# SpectraPCB.net
KiCad netlist of a schematic drawn in EAGLE
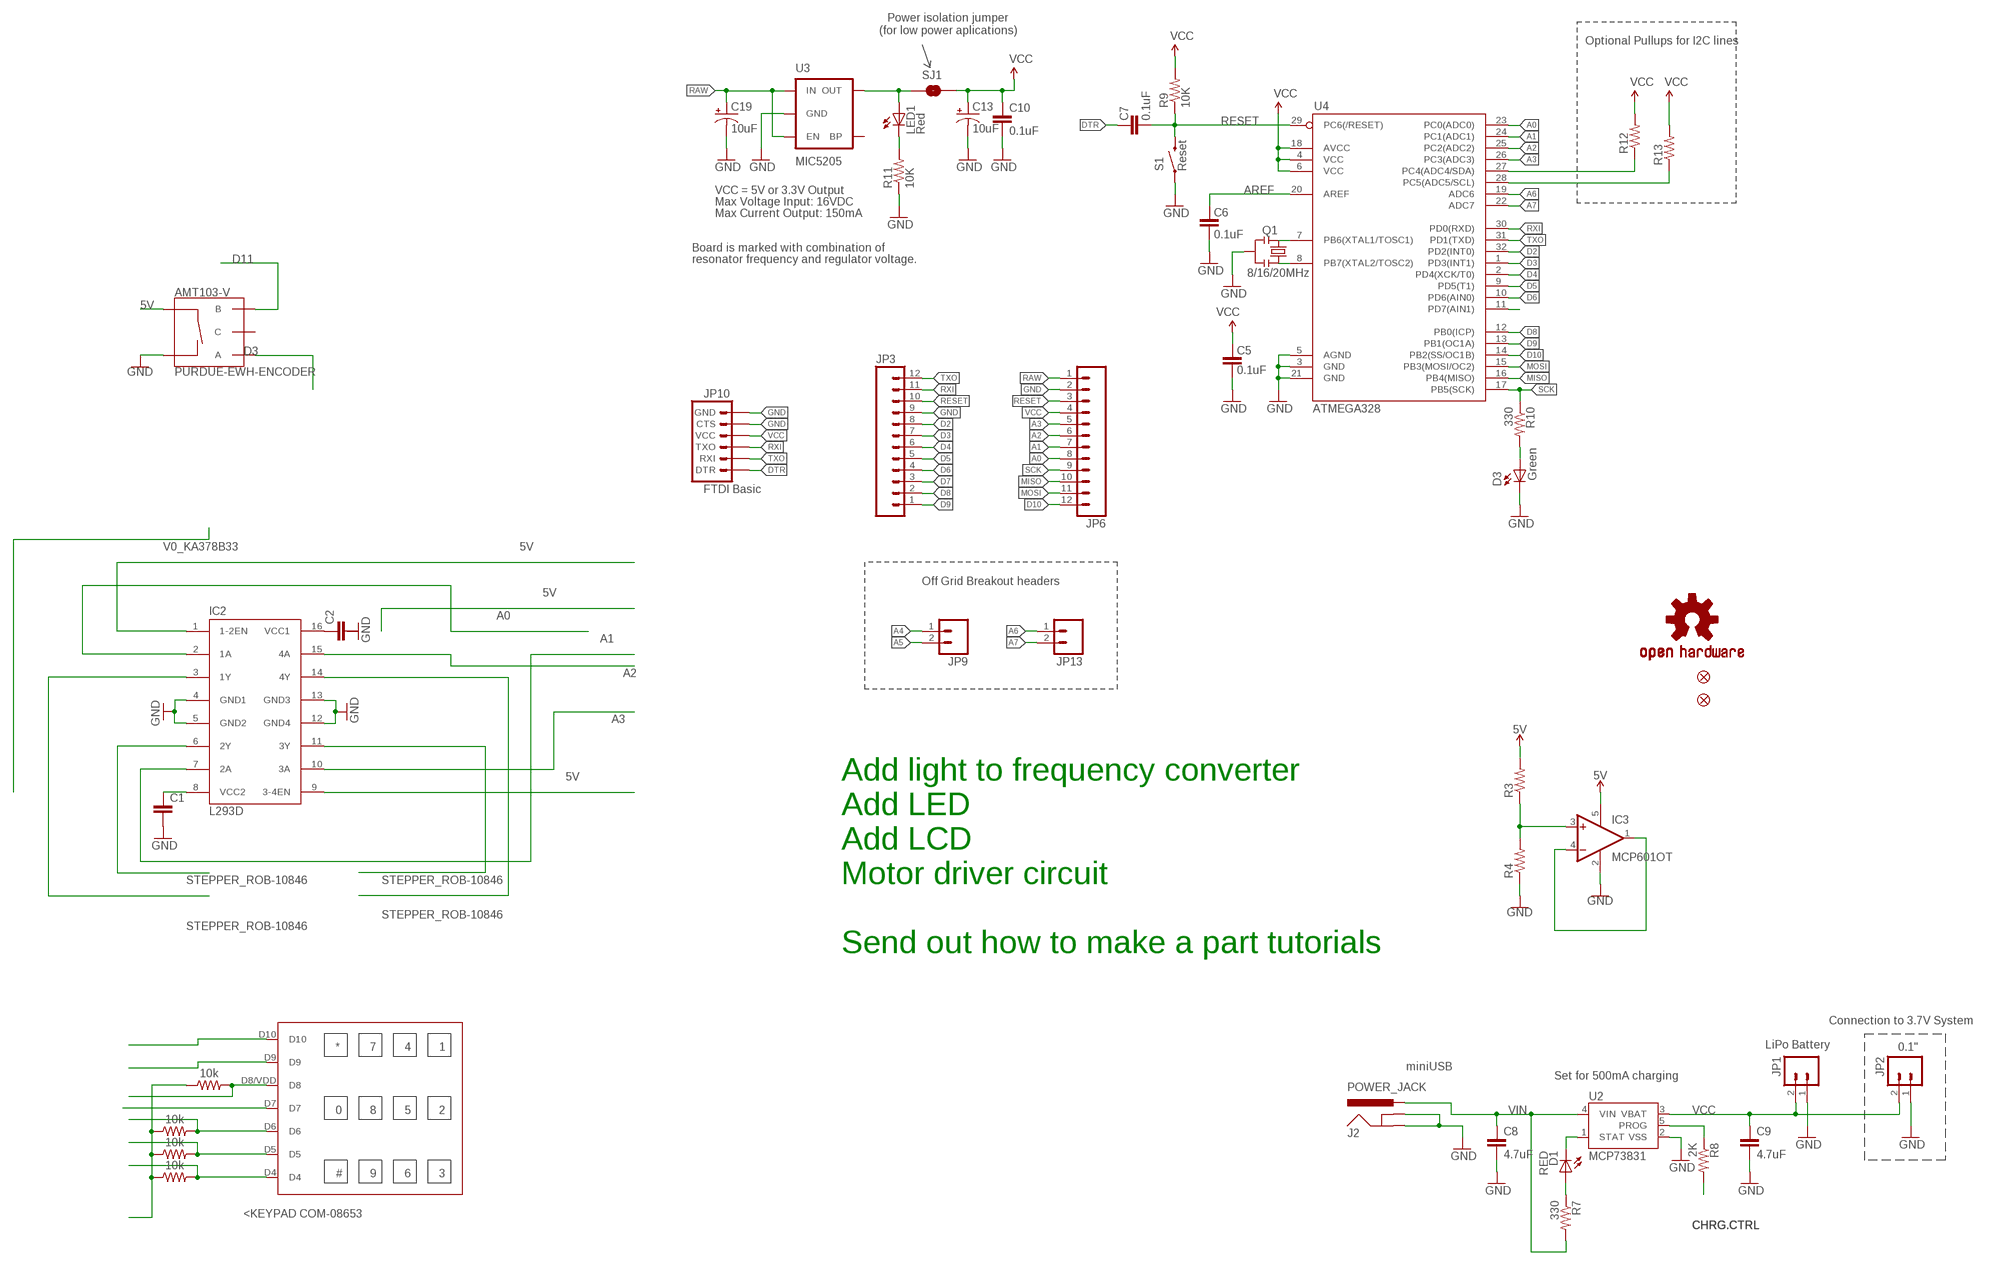
[diagram p0: schematic, sheet 1]

(export (version "E")
  (design (tool "Eeschema 10.0.6"))
  (components
    (comp (ref "AMT103-V")
      (value "PURDUE-EWH-ENCODER")
      (footprint "eagle-import:PURDUE-EWH-ENCODER")
      (libsource (lib "eagle-import") (part "PURDUE-EWH-ENCODER"))
    )
    (comp (ref "C1")
      (value "C-EUC0603")
      (footprint "eagle-import:C0603")
      (libsource (lib "eagle-import") (part "C-EUC0603"))
    )
    (comp (ref "C2")
      (value "C-EUC0402")
      (footprint "eagle-import:C0402")
      (libsource (lib "eagle-import") (part "C-EUC0402"))
    )
    (comp (ref "C5")
      (value "0.1uF")
      (footprint "eagle-import:0603-CAP")
      (libsource (lib "eagle-import") (part "CAP0603-CAP"))
    )
    (comp (ref "C6")
      (value "0.1uF")
      (footprint "eagle-import:0603-CAP")
      (libsource (lib "eagle-import") (part "CAP0603-CAP"))
    )
    (comp (ref "C7")
      (value "0.1uF")
      (footprint "eagle-import:0603-CAP")
      (libsource (lib "eagle-import") (part "CAP0603-CAP"))
    )
    (comp (ref "C8")
      (value "4.7uF")
      (footprint "eagle-import:0402-CAP")
      (libsource (lib "eagle-import") (part "CAP0402-CAP"))
    )
    (comp (ref "C9")
      (value "4.7uF")
      (footprint "eagle-import:0402-CAP")
      (libsource (lib "eagle-import") (part "CAP0402-CAP"))
    )
    (comp (ref "C10")
      (value "0.1uF")
      (footprint "eagle-import:0603-CAP")
      (libsource (lib "eagle-import") (part "CAP0603-CAP"))
    )
    (comp (ref "C13")
      (value "10uF")
      (footprint "eagle-import:EIA3216")
      (libsource (lib "eagle-import") (part "CAP_POL1206"))
    )
    (comp (ref "C19")
      (value "10uF")
      (footprint "eagle-import:EIA3216")
      (libsource (lib "eagle-import") (part "CAP_POL1206"))
    )
    (comp (ref "D1")
      (value "RED")
      (footprint "eagle-import:LED-0603")
      (libsource (lib "eagle-import") (part "LED0603"))
    )
    (comp (ref "D3")
      (value "Green")
      (footprint "eagle-import:0603-LED-ALT1")
      (libsource (lib "eagle-import") (part "LED"))
    )
    (comp (ref "IC2")
      (value "L293D")
      (footprint "eagle-import:DIL16")
      (libsource (lib "eagle-import") (part "L293D"))
    )
    (comp (ref "IC3")
      (value "MCP601OT")
      (footprint "eagle-import:SOT23-5")
      (libsource (lib "eagle-import") (part "MCP601OT"))
    )
    (comp (ref "J2")
      (value "POWER_JACK")
      (footprint "eagle-import:POWER_JACK_PTH")
      (libsource (lib "eagle-import") (part "POWER_JACK"))
    )
    (comp (ref "JP1")
      (value "LiPo Battery")
      (footprint "eagle-import:JST-2-SMD")
      (libsource (lib "eagle-import") (part "M02-JST-2MM-SMT"))
    )
    (comp (ref "JP2")
      (value "M02PTH")
      (footprint "eagle-import:1X02")
      (libsource (lib "eagle-import") (part "M02PTH"))
    )
    (comp (ref "JP3")
      (value "M12PTH")
      (footprint "eagle-import:1X12")
      (libsource (lib "eagle-import") (part "M12PTH"))
    )
    (comp (ref "JP6")
      (value "M12PTH")
      (footprint "eagle-import:1X12")
      (libsource (lib "eagle-import") (part "M12PTH"))
    )
    (comp (ref "JP9")
      (value "M02PTH")
      (footprint "eagle-import:1X02")
      (libsource (lib "eagle-import") (part "M02PTH"))
    )
    (comp (ref "JP10")
      (value "FTDI Basic")
      (footprint "eagle-import:1X06")
      (libsource (lib "eagle-import") (part "ARDUINO_SERIAL_PROGRAMPTH"))
    )
    (comp (ref "JP11")
      (value "FIDUCIALUFIDUCIAL")
      (footprint "eagle-import:MICRO-FIDUCIAL")
      (libsource (lib "eagle-import") (part "FIDUCIALUFIDUCIAL"))
    )
    (comp (ref "JP12")
      (value "FIDUCIALUFIDUCIAL")
      (footprint "eagle-import:MICRO-FIDUCIAL")
      (libsource (lib "eagle-import") (part "FIDUCIALUFIDUCIAL"))
    )
    (comp (ref "JP13")
      (value "M02PTH")
      (footprint "eagle-import:1X02")
      (libsource (lib "eagle-import") (part "M02PTH"))
    )
    (comp (ref "LED1")
      (value "Red")
      (footprint "eagle-import:0603-LED-ALT1")
      (libsource (lib "eagle-import") (part "LED"))
    )
    (comp (ref "Q1")
      (value "8/16/20MHz")
      (footprint "eagle-import:RESONATOR-SMD-1_1")
      (libsource (lib "eagle-import") (part "RESONATOR1{colon}1"))
    )
    (comp (ref "R1")
      (value "10k")
      (footprint "eagle-import:0603")
      (libsource (lib "eagle-import") (part "10KOHM-0603-1/10W-1%"))
    )
    (comp (ref "R2")
      (value "10k")
      (footprint "eagle-import:0603")
      (libsource (lib "eagle-import") (part "10KOHM-0603-1/10W-1%"))
    )
    (comp (ref "R3")
      (value "R-US_R0402")
      (footprint "eagle-import:R0402")
      (libsource (lib "eagle-import") (part "R-US_R0402"))
    )
    (comp (ref "R4")
      (value "R-US_R0402")
      (footprint "eagle-import:R0402")
      (libsource (lib "eagle-import") (part "R-US_R0402"))
    )
    (comp (ref "R5")
      (value "10k")
      (footprint "eagle-import:0603")
      (libsource (lib "eagle-import") (part "10KOHM-0603-1/10W-1%"))
    )
    (comp (ref "R6")
      (value "10k")
      (footprint "eagle-import:0603")
      (libsource (lib "eagle-import") (part "10KOHM-0603-1/10W-1%"))
    )
    (comp (ref "R7")
      (value "330")
      (footprint "eagle-import:0402-RES")
      (libsource (lib "eagle-import") (part "RESISTOR0402-RES"))
    )
    (comp (ref "R8")
      (value "2K")
      (footprint "eagle-import:0402-RES")
      (libsource (lib "eagle-import") (part "RESISTOR0402-RES"))
    )
    (comp (ref "R9")
      (value "10K")
      (footprint "eagle-import:0603-RES")
      (libsource (lib "eagle-import") (part "RESISTOR0603-RES"))
    )
    (comp (ref "R10")
      (value "330")
      (footprint "eagle-import:0603-RES")
      (libsource (lib "eagle-import") (part "RESISTOR0603-RES"))
    )
    (comp (ref "R11")
      (value "10K")
      (footprint "eagle-import:0603-RES")
      (libsource (lib "eagle-import") (part "RESISTOR0603-RES"))
    )
    (comp (ref "R12")
      (value "RESISTOR0603-RES")
      (footprint "eagle-import:0603-RES")
      (libsource (lib "eagle-import") (part "RESISTOR0603-RES"))
    )
    (comp (ref "R13")
      (value "RESISTOR0603-RES")
      (footprint "eagle-import:0603-RES")
      (libsource (lib "eagle-import") (part "RESISTOR0603-RES"))
    )
    (comp (ref "S1")
      (value "Reset")
      (footprint "eagle-import:TACTILE-SWITCH-SMD-ALT01")
      (libsource (lib "eagle-import") (part "SWITCH-MOMENTARY-2SMD-ALT01"))
    )
    (comp (ref "SJ1")
      (value "SOLDERJUMPERNC")
      (footprint "eagle-import:SJ_2S")
      (libsource (lib "eagle-import") (part "SOLDERJUMPERNC"))
    )
    (comp (ref "U$1")
      (value "EWH_KEYPAD")
      (footprint "eagle-import:EWH_KEYPAD")
      (libsource (lib "eagle-import") (part "EWH_KEYPAD"))
    )
    (comp (ref "U$3")
      (value "OSHW-LOGOS")
      (footprint "eagle-import:OSHW-LOGO-S")
      (libsource (lib "eagle-import") (part "OSHW-LOGOS"))
    )
    (comp (ref "U2")
      (value "MCP73831")
      (footprint "eagle-import:SOT23-5")
      (libsource (lib "eagle-import") (part "MCP73831"))
    )
    (comp (ref "U3")
      (value "MIC5205")
      (footprint "eagle-import:SOT23-5")
      (libsource (lib "eagle-import") (part "V_REG_LDOSMD"))
    )
    (comp (ref "U4")
      (value "ATMEGA328")
      (footprint "eagle-import:TQFP32-08")
      (libsource (lib "eagle-import") (part "ATMEGA168"))
    )
  )
  (nets
    (net (code "1") (name "/AREF") (class "Default")
      (node (ref "C6") (pin "2") (pinfunction "2_2") (pintype "passive"))
      (node (ref "U4") (pin "20") (pinfunction "AREF_20") (pintype "bidirectional"))
    )
    (net (code "2") (name "/CHRG.CTRL") (class "Default")
      (node (ref "R8") (pin "2") (pinfunction "2_2") (pintype "passive"))
      (node (ref "U4") (pin "11") (pinfunction "PD7(AIN1)_11") (pintype "bidirectional"))
    )
    (net (code "3") (name "/D11") (class "Default")
      (node (ref "AMT103-V") (pin "B") (pinfunction "B_B") (pintype "bidirectional"))
    )
    (net (code "4") (name "/STEPPER_ROB-10846") (class "Default")
      (node (ref "IC2") (pin "11") (pinfunction "3Y_11") (pintype "output"))
      (node (ref "IC2") (pin "14") (pinfunction "4Y_14") (pintype "output"))
      (node (ref "IC2") (pin "3") (pinfunction "1Y_3") (pintype "output"))
      (node (ref "IC2") (pin "6") (pinfunction "2Y_6") (pintype "output"))
    )
    (net (code "6") (name "/VIN") (class "Default")
      (node (ref "C8") (pin "1") (pinfunction "1_1") (pintype "passive"))
      (node (ref "J2") (pin "PWR") (pinfunction "PWR_PWR") (pintype "bidirectional"))
      (node (ref "R7") (pin "2") (pinfunction "2_2") (pintype "passive"))
      (node (ref "U2") (pin "4") (pinfunction "VIN_4") (pintype "power_in"))
    )
    (net (code "7") (name "5V") (class "Default")
      (node (ref "AMT103-V") (pin "SW+") (pinfunction "SW+_SW+") (pintype "bidirectional"))
      (node (ref "IC2") (pin "1") (pinfunction "1-2EN_1") (pintype "input"))
      (node (ref "IC2") (pin "9") (pinfunction "3-4EN_9") (pintype "input"))
      (node (ref "IC3") (pin "5") (pinfunction "V+_5") (pintype "power_in"))
      (node (ref "R3") (pin "2") (pinfunction "2_2") (pintype "passive"))
    )
    (net (code "8") (name "A0") (class "Default")
      (node (ref "IC2") (pin "2") (pinfunction "1A_2") (pintype "input"))
      (node (ref "JP6") (pin "8") (pinfunction "8_8") (pintype "passive"))
      (node (ref "U4") (pin "23") (pinfunction "PC0(ADC0)_23") (pintype "bidirectional"))
    )
    (net (code "9") (name "A1") (class "Default")
      (node (ref "IC2") (pin "7") (pinfunction "2A_7") (pintype "input"))
      (node (ref "JP6") (pin "7") (pinfunction "7_7") (pintype "passive"))
      (node (ref "U4") (pin "24") (pinfunction "PC1(ADC1)_24") (pintype "bidirectional"))
    )
    (net (code "10") (name "A2") (class "Default")
      (node (ref "IC2") (pin "15") (pinfunction "4A_15") (pintype "input"))
      (node (ref "JP6") (pin "6") (pinfunction "6_6") (pintype "passive"))
      (node (ref "U4") (pin "25") (pinfunction "PC2(ADC2)_25") (pintype "bidirectional"))
    )
    (net (code "11") (name "A3") (class "Default")
      (node (ref "IC2") (pin "10") (pinfunction "3A_10") (pintype "input"))
      (node (ref "JP6") (pin "5") (pinfunction "5_5") (pintype "passive"))
      (node (ref "U4") (pin "26") (pinfunction "PC3(ADC3)_26") (pintype "bidirectional"))
    )
    (net (code "12") (name "A4") (class "Default")
      (node (ref "JP9") (pin "1") (pinfunction "1_1") (pintype "passive"))
      (node (ref "R12") (pin "1") (pinfunction "1_1") (pintype "passive"))
      (node (ref "U4") (pin "27") (pinfunction "PC4(ADC4/SDA)_27") (pintype "bidirectional"))
    )
    (net (code "13") (name "A5") (class "Default")
      (node (ref "JP9") (pin "2") (pinfunction "2_2") (pintype "passive"))
      (node (ref "R13") (pin "1") (pinfunction "1_1") (pintype "passive"))
      (node (ref "U4") (pin "28") (pinfunction "PC5(ADC5/SCL)_28") (pintype "bidirectional"))
    )
    (net (code "14") (name "A6") (class "Default")
      (node (ref "JP13") (pin "1") (pinfunction "1_1") (pintype "passive"))
      (node (ref "U4") (pin "19") (pinfunction "ADC6_19") (pintype "bidirectional"))
    )
    (net (code "15") (name "A7") (class "Default")
      (node (ref "JP13") (pin "2") (pinfunction "2_2") (pintype "passive"))
      (node (ref "U4") (pin "22") (pinfunction "ADC7_22") (pintype "bidirectional"))
    )
    (net (code "16") (name "D2") (class "Default")
      (node (ref "JP3") (pin "8") (pinfunction "8_8") (pintype "passive"))
      (node (ref "U4") (pin "32") (pinfunction "PD2(INT0)_32") (pintype "bidirectional"))
    )
    (net (code "17") (name "D3") (class "Default")
      (node (ref "AMT103-V") (pin "A") (pinfunction "A_A") (pintype "bidirectional"))
      (node (ref "JP3") (pin "7") (pinfunction "7_7") (pintype "passive"))
      (node (ref "U4") (pin "1") (pinfunction "PD3(INT1)_1") (pintype "bidirectional"))
    )
    (net (code "18") (name "D4") (class "Default")
      (node (ref "JP3") (pin "6") (pinfunction "6_6") (pintype "passive"))
      (node (ref "U4") (pin "2") (pinfunction "PD4(XCK/T0)_2") (pintype "bidirectional"))
    )
    (net (code "19") (name "D5") (class "Default")
      (node (ref "JP3") (pin "5") (pinfunction "5_5") (pintype "passive"))
      (node (ref "U4") (pin "9") (pinfunction "PD5(T1)_9") (pintype "bidirectional"))
    )
    (net (code "20") (name "D6") (class "Default")
      (node (ref "JP3") (pin "4") (pinfunction "4_4") (pintype "passive"))
      (node (ref "U4") (pin "10") (pinfunction "PD6(AIN0)_10") (pintype "bidirectional"))
    )
    (net (code "21") (name "D7") (class "Default")
      (node (ref "JP3") (pin "3") (pinfunction "3_3") (pintype "passive"))
    )
    (net (code "22") (name "D8") (class "Default")
      (node (ref "JP3") (pin "2") (pinfunction "2_2") (pintype "passive"))
      (node (ref "U4") (pin "12") (pinfunction "PB0(ICP)_12") (pintype "bidirectional"))
    )
    (net (code "23") (name "D9") (class "Default")
      (node (ref "JP3") (pin "1") (pinfunction "1_1") (pintype "passive"))
      (node (ref "U4") (pin "13") (pinfunction "PB1(OC1A)_13") (pintype "bidirectional"))
    )
    (net (code "24") (name "D10") (class "Default")
      (node (ref "JP6") (pin "12") (pinfunction "12_12") (pintype "passive"))
      (node (ref "U4") (pin "14") (pinfunction "PB2(SS/OC1B)_14") (pintype "bidirectional"))
    )
    (net (code "25") (name "DTR") (class "Default")
      (node (ref "C7") (pin "2") (pinfunction "2_2") (pintype "passive"))
      (node (ref "JP10") (pin "1") (pinfunction "DTR_1") (pintype "passive"))
    )
    (net (code "26") (name "GND") (class "Default")
      (node (ref "AMT103-V") (pin "SW-") (pinfunction "SW-_SW-") (pintype "bidirectional"))
      (node (ref "C1") (pin "2") (pinfunction "2_2") (pintype "passive"))
      (node (ref "C10") (pin "2") (pinfunction "2_2") (pintype "passive"))
      (node (ref "C13") (pin "C") (pinfunction "-_C") (pintype "passive"))
      (node (ref "C19") (pin "C") (pinfunction "-_C") (pintype "passive"))
      (node (ref "C5") (pin "1") (pinfunction "1_1") (pintype "passive"))
      (node (ref "C6") (pin "1") (pinfunction "1_1") (pintype "passive"))
      (node (ref "C8") (pin "2") (pinfunction "2_2") (pintype "passive"))
      (node (ref "C9") (pin "2") (pinfunction "2_2") (pintype "passive"))
      (node (ref "D3") (pin "C") (pinfunction "C_C") (pintype "passive"))
      (node (ref "IC2") (pin "12") (pinfunction "GND4_12") (pintype "power_in"))
      (node (ref "IC2") (pin "13") (pinfunction "GND3_13") (pintype "power_in"))
      (node (ref "IC2") (pin "4") (pinfunction "GND1_4") (pintype "power_in"))
      (node (ref "IC2") (pin "5") (pinfunction "GND2_5") (pintype "power_in"))
      (node (ref "IC3") (pin "2") (pinfunction "V-_2") (pintype "power_in"))
      (node (ref "J2") (pin "GND") (pinfunction "GND_GND") (pintype "bidirectional"))
      (node (ref "J2") (pin "GNDBREAK") (pinfunction "GNDBREAK_GNDBREAK") (pintype "bidirectional"))
      (node (ref "JP1") (pin "1") (pinfunction "1_1") (pintype "passive"))
      (node (ref "JP10") (pin "5") (pinfunction "CTS_5") (pintype "passive"))
      (node (ref "JP10") (pin "6") (pinfunction "GND_6") (pintype "passive"))
      (node (ref "JP2") (pin "1") (pinfunction "1_1") (pintype "passive"))
      (node (ref "JP3") (pin "9") (pinfunction "9_9") (pintype "passive"))
      (node (ref "JP6") (pin "2") (pinfunction "2_2") (pintype "passive"))
      (node (ref "Q1") (pin "2") (pinfunction "2_2") (pintype "passive"))
      (node (ref "R11") (pin "1") (pinfunction "1_1") (pintype "passive"))
      (node (ref "R4") (pin "1") (pinfunction "1_1") (pintype "passive"))
      (node (ref "S1") (pin "1") (pinfunction "1_1") (pintype "passive"))
      (node (ref "S1") (pin "2") (pinfunction "1_2") (pintype "passive"))
      (node (ref "U2") (pin "2") (pinfunction "VSS_2") (pintype "power_in"))
      (node (ref "U3") (pin "2") (pinfunction "GND_2") (pintype "input"))
      (node (ref "U4") (pin "21") (pinfunction "GND_21") (pintype "bidirectional"))
      (node (ref "U4") (pin "3") (pinfunction "GND_3") (pintype "bidirectional"))
      (node (ref "U4") (pin "5") (pinfunction "AGND_5") (pintype "bidirectional"))
    )
    (net (code "27") (name "MISO") (class "Default")
      (node (ref "JP6") (pin "10") (pinfunction "10_10") (pintype "passive"))
      (node (ref "U4") (pin "16") (pinfunction "PB4(MISO)_16") (pintype "bidirectional"))
    )
    (net (code "28") (name "MOSI") (class "Default")
      (node (ref "JP6") (pin "11") (pinfunction "11_11") (pintype "passive"))
      (node (ref "U4") (pin "15") (pinfunction "PB3(MOSI/OC2)_15") (pintype "bidirectional"))
    )
    (net (code "29") (name "Net-(D1-PadA)") (class "Default")
      (node (ref "D1") (pin "A") (pinfunction "A_A") (pintype "passive"))
      (node (ref "R7") (pin "1") (pinfunction "1_1") (pintype "passive"))
    )
    (net (code "30") (name "Net-(D3-PadA)") (class "Default")
      (node (ref "D3") (pin "A") (pinfunction "A_A") (pintype "passive"))
      (node (ref "R10") (pin "2") (pinfunction "2_2") (pintype "passive"))
    )
    (net (code "31") (name "Net-(IC2-VCC1)") (class "Default")
      (node (ref "C2") (pin "1") (pinfunction "1_1") (pintype "passive"))
      (node (ref "IC2") (pin "16") (pinfunction "VCC1_16") (pintype "power_in"))
    )
    (net (code "32") (name "Net-(IC2-VCC2)") (class "Default")
      (node (ref "C1") (pin "1") (pinfunction "1_1") (pintype "passive"))
      (node (ref "IC2") (pin "8") (pinfunction "VCC2_8") (pintype "power_in"))
    )
    (net (code "33") (name "Net-(IC3-+IN)") (class "Default")
      (node (ref "IC3") (pin "3") (pinfunction "+IN_3") (pintype "input"))
      (node (ref "R3") (pin "1") (pinfunction "1_1") (pintype "passive"))
      (node (ref "R4") (pin "2") (pinfunction "2_2") (pintype "passive"))
    )
    (net (code "34") (name "Net-(IC3--IN)") (class "Default")
      (node (ref "IC3") (pin "1") (pinfunction "OUT_1") (pintype "output"))
      (node (ref "IC3") (pin "4") (pinfunction "-IN_4") (pintype "input"))
    )
    (net (code "35") (name "Net-(LED1-PadC)") (class "Default")
      (node (ref "LED1") (pin "C") (pinfunction "C_C") (pintype "passive"))
      (node (ref "R11") (pin "2") (pinfunction "2_2") (pintype "passive"))
    )
    (net (code "36") (name "Net-(R1-Pad1)") (class "Default")
      (node (ref "R1") (pin "1") (pinfunction "1_1") (pintype "passive"))
      (node (ref "R2") (pin "1") (pinfunction "1_1") (pintype "passive"))
      (node (ref "R5") (pin "1") (pinfunction "1_1") (pintype "passive"))
      (node (ref "R6") (pin "1") (pinfunction "1_1") (pintype "passive"))
    )
    (net (code "37") (name "Net-(R2-Pad2)") (class "Default")
      (node (ref "R2") (pin "2") (pinfunction "2_2") (pintype "passive"))
      (node (ref "U$1") (pin "D6") (pinfunction "D6_D6") (pintype "bidirectional"))
    )
    (net (code "38") (name "Net-(R5-Pad2)") (class "Default")
      (node (ref "R5") (pin "2") (pinfunction "2_2") (pintype "passive"))
      (node (ref "U$1") (pin "D5") (pinfunction "D5_D5") (pintype "bidirectional"))
    )
    (net (code "39") (name "Net-(R6-Pad2)") (class "Default")
      (node (ref "R6") (pin "2") (pinfunction "2_2") (pintype "passive"))
      (node (ref "U$1") (pin "D4") (pinfunction "D4_D4") (pintype "bidirectional"))
    )
    (net (code "40") (name "Net-(U$1-D8)") (class "Default")
      (node (ref "R1") (pin "2") (pinfunction "2_2") (pintype "passive"))
      (node (ref "U$1") (pin "D8/VDD") (pinfunction "D8_D8/VDD") (pintype "bidirectional"))
    )
    (net (code "41") (name "Net-(U2-PROG)") (class "Default")
      (node (ref "R8") (pin "1") (pinfunction "1_1") (pintype "passive"))
      (node (ref "U2") (pin "5") (pinfunction "PROG_5") (pintype "input"))
    )
    (net (code "42") (name "Net-(U2-STAT)") (class "Default")
      (node (ref "D1") (pin "C") (pinfunction "C_C") (pintype "passive"))
      (node (ref "U2") (pin "1") (pinfunction "STAT_1") (pintype "output"))
    )
    (net (code "43") (name "Net-(U3-OUT)") (class "Default")
      (node (ref "LED1") (pin "A") (pinfunction "A_A") (pintype "passive"))
      (node (ref "SJ1") (pin "1") (pinfunction "1_1") (pintype "passive"))
      (node (ref "U3") (pin "5") (pinfunction "OUT_5") (pintype "passive"))
    )
    (net (code "44") (name "Net-(U4-PB6(XTAL1{slash}TOSC1))") (class "Default")
      (node (ref "Q1") (pin "1") (pinfunction "1_1") (pintype "passive"))
      (node (ref "U4") (pin "7") (pinfunction "PB6(XTAL1/TOSC1)_7") (pintype "bidirectional"))
    )
    (net (code "45") (name "Net-(U4-PB7(XTAL2{slash}TOSC2))") (class "Default")
      (node (ref "Q1") (pin "3") (pinfunction "3_3") (pintype "passive"))
      (node (ref "U4") (pin "8") (pinfunction "PB7(XTAL2/TOSC2)_8") (pintype "bidirectional"))
    )
    (net (code "46") (name "RAW") (class "Default")
      (node (ref "C19") (pin "A") (pinfunction "+_A") (pintype "passive"))
      (node (ref "JP6") (pin "1") (pinfunction "1_1") (pintype "passive"))
      (node (ref "U3") (pin "1") (pinfunction "IN_1") (pintype "input"))
      (node (ref "U3") (pin "3") (pinfunction "EN_3") (pintype "input"))
    )
    (net (code "47") (name "RESET") (class "Default")
      (node (ref "C7") (pin "1") (pinfunction "1_1") (pintype "passive"))
      (node (ref "JP3") (pin "10") (pinfunction "10_10") (pintype "passive"))
      (node (ref "JP6") (pin "3") (pinfunction "3_3") (pintype "passive"))
      (node (ref "R9") (pin "1") (pinfunction "1_1") (pintype "passive"))
      (node (ref "S1") (pin "3") (pinfunction "2_3") (pintype "passive"))
      (node (ref "S1") (pin "4") (pinfunction "2_4") (pintype "passive"))
      (node (ref "U4") (pin "29") (pinfunction "PC6(/RESET)_29") (pintype "bidirectional"))
    )
    (net (code "48") (name "RXI") (class "Default")
      (node (ref "JP10") (pin "3") (pinfunction "TXO_3") (pintype "passive"))
      (node (ref "JP3") (pin "11") (pinfunction "11_11") (pintype "passive"))
      (node (ref "U4") (pin "30") (pinfunction "PD0(RXD)_30") (pintype "bidirectional"))
    )
    (net (code "49") (name "SCK") (class "Default")
      (node (ref "JP6") (pin "9") (pinfunction "9_9") (pintype "passive"))
      (node (ref "R10") (pin "1") (pinfunction "1_1") (pintype "passive"))
      (node (ref "U4") (pin "17") (pinfunction "PB5(SCK)_17") (pintype "bidirectional"))
    )
    (net (code "50") (name "TXO") (class "Default")
      (node (ref "JP10") (pin "2") (pinfunction "RXI_2") (pintype "passive"))
      (node (ref "JP3") (pin "12") (pinfunction "12_12") (pintype "passive"))
      (node (ref "U4") (pin "31") (pinfunction "PD1(TXD)_31") (pintype "bidirectional"))
    )
    (net (code "51") (name "VCC") (class "Default")
      (node (ref "C10") (pin "1") (pinfunction "1_1") (pintype "passive"))
      (node (ref "C13") (pin "A") (pinfunction "+_A") (pintype "passive"))
      (node (ref "C5") (pin "2") (pinfunction "2_2") (pintype "passive"))
      (node (ref "C9") (pin "1") (pinfunction "1_1") (pintype "passive"))
      (node (ref "JP1") (pin "2") (pinfunction "2_2") (pintype "passive"))
      (node (ref "JP10") (pin "4") (pinfunction "VCC_4") (pintype "passive"))
      (node (ref "JP2") (pin "2") (pinfunction "2_2") (pintype "passive"))
      (node (ref "JP6") (pin "4") (pinfunction "4_4") (pintype "passive"))
      (node (ref "R12") (pin "2") (pinfunction "2_2") (pintype "passive"))
      (node (ref "R13") (pin "2") (pinfunction "2_2") (pintype "passive"))
      (node (ref "R9") (pin "2") (pinfunction "2_2") (pintype "passive"))
      (node (ref "SJ1") (pin "2") (pinfunction "2_2") (pintype "passive"))
      (node (ref "U2") (pin "3") (pinfunction "VBAT_3") (pintype "power_in"))
      (node (ref "U4") (pin "18") (pinfunction "AVCC_18") (pintype "bidirectional"))
      (node (ref "U4") (pin "4") (pinfunction "VCC_4") (pintype "bidirectional"))
      (node (ref "U4") (pin "6") (pinfunction "VCC_6") (pintype "bidirectional"))
    )
    (net (code "52") (name "unconnected-(AMT103-V-PadC)") (class "Default")
      (node (ref "AMT103-V") (pin "C") (pinfunction "C_C") (pintype "bidirectional"))
    )
    (net (code "53") (name "unconnected-(C2-Pad2)") (class "Default")
      (node (ref "C2") (pin "2") (pinfunction "2_2") (pintype "passive"))
    )
    (net (code "54") (name "unconnected-(U$1-PadD7)") (class "Default")
      (node (ref "U$1") (pin "D7") (pinfunction "D7_D7") (pintype "bidirectional"))
    )
    (net (code "55") (name "unconnected-(U$1-PadD9)") (class "Default")
      (node (ref "U$1") (pin "D9") (pinfunction "D9_D9") (pintype "bidirectional"))
    )
    (net (code "56") (name "unconnected-(U$1-PadD10)") (class "Default")
      (node (ref "U$1") (pin "D10") (pinfunction "D10_D10") (pintype "bidirectional"))
    )
    (net (code "57") (name "unconnected-(U3-BP-Pad4)") (class "Default")
      (node (ref "U3") (pin "4") (pinfunction "BP_4") (pintype "input"))
    )
  )
)
